# tvout_terminal_v1_0.net
KiCad netlist of a schematic drawn in EAGLE
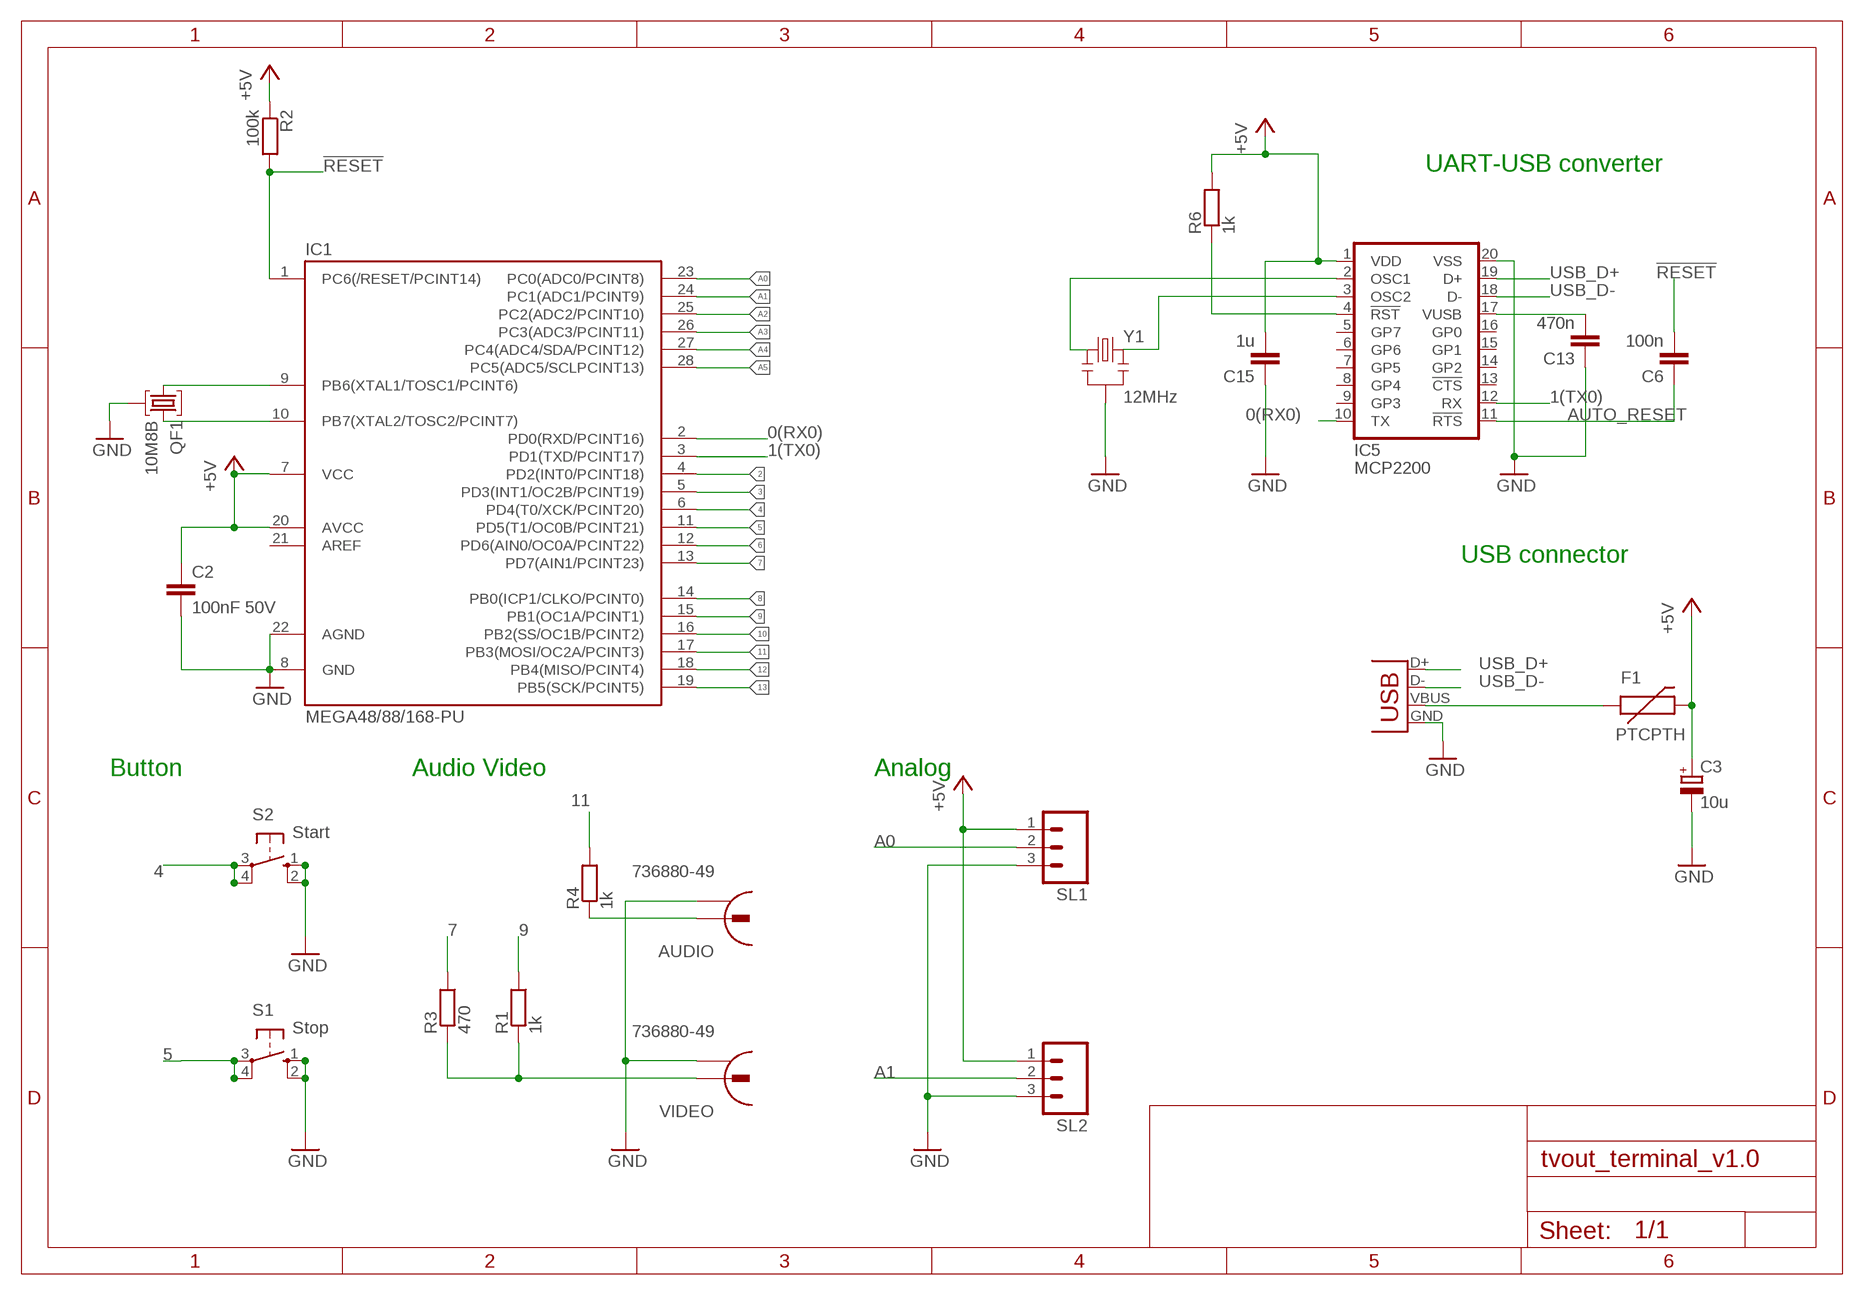
[diagram p0: schematic, sheet 1]

(export (version "E")
  (design (tool "Eeschema 10.0.6"))
  (components
    (comp (ref "AUDIO")
      (value "736880-49")
      (footprint "eagle-import:736880-49")
      (libsource (lib "eagle-import") (part "736880-49"))
    )
    (comp (ref "C2")
      (value "100nF 50V")
      (footprint "eagle-import:C025-025X050")
      (libsource (lib "eagle-import") (part "C-EU025-025X050"))
    )
    (comp (ref "C3")
      (value "10u")
      (footprint "eagle-import:E2,5-7")
      (libsource (lib "eagle-import") (part "CPOL-EUE2.5-7"))
    )
    (comp (ref "C6")
      (value "100n")
      (footprint "eagle-import:CAP-PTH-SMALL")
      (libsource (lib "eagle-import") (part "CAPPTH"))
    )
    (comp (ref "C13")
      (value "470n")
      (footprint "eagle-import:CAP-PTH-SMALL")
      (libsource (lib "eagle-import") (part "CAPPTH"))
    )
    (comp (ref "C15")
      (value "1u")
      (footprint "eagle-import:CAP-PTH-SMALL")
      (libsource (lib "eagle-import") (part "CAPPTH"))
    )
    (comp (ref "F1")
      (value "PTCPTH")
      (footprint "eagle-import:PTC")
      (libsource (lib "eagle-import") (part "PTCPTH"))
    )
    (comp (ref "IC1")
      (value "MEGA48/88/168-PU")
      (footprint "eagle-import:DIL28-3")
      (libsource (lib "eagle-import") (part "MEGA48/88/168-PU"))
    )
    (comp (ref "IC5")
      (value "MCP2200")
      (footprint "eagle-import:SO20")
      (libsource (lib "eagle-import") (part "MCP2200"))
    )
    (comp (ref "QF1")
      (value "10M8B")
      (footprint "eagle-import:HC49U")
      (fields (field (name "OC_FARNELL") "1448129"))
      (libsource (lib "eagle-import") (part "10MB8"))
    )
    (comp (ref "R1")
      (value "1k")
      (footprint "eagle-import:RES-AXIAL-0.4")
      (libsource (lib "eagle-import") (part "RESISTOR"))
    )
    (comp (ref "R2")
      (value "100k")
      (footprint "eagle-import:RES-AXIAL-0.4")
      (libsource (lib "eagle-import") (part "RESISTOR"))
    )
    (comp (ref "R3")
      (value "470")
      (footprint "eagle-import:RES-AXIAL-0.4")
      (libsource (lib "eagle-import") (part "RESISTOR"))
    )
    (comp (ref "R4")
      (value "1k")
      (footprint "eagle-import:RES-AXIAL-0.4")
      (libsource (lib "eagle-import") (part "RESISTOR"))
    )
    (comp (ref "R6")
      (value "1k")
      (footprint "eagle-import:RES-AXIAL-0.4")
      (libsource (lib "eagle-import") (part "RESISTOR"))
    )
    (comp (ref "S1")
      (value "Stop")
      (footprint "eagle-import:B3F-10XX")
      (fields (field (name "MPN") "B3F-1000"))
      (libsource (lib "eagle-import") (part "10-XX"))
    )
    (comp (ref "S2")
      (value "Start")
      (footprint "eagle-import:B3F-10XX")
      (fields (field (name "MPN") "B3F-1000"))
      (libsource (lib "eagle-import") (part "10-XX"))
    )
    (comp (ref "SL1")
      (value "M03")
      (footprint "eagle-import:03P")
      (fields (field (name "OC_FARNELL") "1675765"))
      (libsource (lib "eagle-import") (part "M03"))
    )
    (comp (ref "SL2")
      (value "M03")
      (footprint "eagle-import:03P")
      (libsource (lib "eagle-import") (part "M03"))
    )
    (comp (ref "VIDEO")
      (value "736880-49")
      (footprint "eagle-import:736880-49")
      (libsource (lib "eagle-import") (part "736880-49"))
    )
    (comp (ref "X3")
      (value "USB")
      (footprint "eagle-import:USB-B-PTH")
      (libsource (lib "eagle-import") (part "USBPTH"))
    )
    (comp (ref "Y1")
      (value "12MHz")
      (footprint "eagle-import:HC49U-V-RESONATOR")
      (libsource (lib "eagle-import") (part "CRYSTAL-RESONATOR"))
    )
  )
  (nets
    (net (code "1") (name "+5V") (class "Default")
      (node (ref "C15") (pin "2") (pinfunction "2_2") (pintype "passive"))
      (node (ref "C2") (pin "1") (pinfunction "1_1") (pintype "passive"))
      (node (ref "C3") (pin "+") (pinfunction "+_+") (pintype "passive"))
      (node (ref "F1") (pin "P$2") (pinfunction "2_P$2") (pintype "bidirectional"))
      (node (ref "IC1") (pin "20") (pinfunction "AVCC_20") (pintype "passive"))
      (node (ref "IC1") (pin "7") (pinfunction "VCC_7") (pintype "power_in"))
      (node (ref "IC5") (pin "1") (pinfunction "VDD_1") (pintype "power_in"))
      (node (ref "R2") (pin "P$1") (pinfunction "1_P$1") (pintype "passive"))
      (node (ref "R6") (pin "P$2") (pinfunction "2_P$2") (pintype "passive"))
      (node (ref "SL1") (pin "1") (pinfunction "1_1") (pintype "passive"))
      (node (ref "SL2") (pin "1") (pinfunction "1_1") (pintype "passive"))
    )
    (net (code "2") (name "/0(RX0)") (class "Default")
      (node (ref "IC1") (pin "2") (pinfunction "PD0(RXD/PCINT16)_2") (pintype "bidirectional"))
      (node (ref "IC5") (pin "10") (pinfunction "TX_10") (pintype "bidirectional"))
    )
    (net (code "3") (name "/1(TX0)") (class "Default")
      (node (ref "IC1") (pin "3") (pinfunction "PD1(TXD/PCINT17)_3") (pintype "bidirectional"))
      (node (ref "IC5") (pin "12") (pinfunction "RX_12") (pintype "bidirectional"))
    )
    (net (code "4") (name "/AUTO_RESET") (class "Default")
      (node (ref "C6") (pin "1") (pinfunction "1_1") (pintype "passive"))
      (node (ref "IC5") (pin "11") (pinfunction "~{RTS}_11") (pintype "bidirectional"))
    )
    (net (code "5") (name "/USB_D+") (class "Default")
      (node (ref "IC5") (pin "19") (pinfunction "D+_19") (pintype "bidirectional"))
      (node (ref "X3") (pin "D+") (pinfunction "D+_D+") (pintype "bidirectional"))
    )
    (net (code "6") (name "/USB_D-") (class "Default")
      (node (ref "IC5") (pin "18") (pinfunction "D-_18") (pintype "bidirectional"))
      (node (ref "X3") (pin "D-") (pinfunction "D-_D-") (pintype "bidirectional"))
    )
    (net (code "7") (name "/~{RESET}") (class "Default")
      (node (ref "C6") (pin "2") (pinfunction "2_2") (pintype "passive"))
      (node (ref "IC1") (pin "1") (pinfunction "PC6(/RESET/PCINT14)_1") (pintype "bidirectional"))
      (node (ref "R2") (pin "P$2") (pinfunction "2_P$2") (pintype "passive"))
    )
    (net (code "8") (name "2") (class "Default")
      (node (ref "IC1") (pin "4") (pinfunction "PD2(INT0/PCINT18)_4") (pintype "bidirectional"))
    )
    (net (code "9") (name "3") (class "Default")
      (node (ref "IC1") (pin "5") (pinfunction "PD3(INT1/OC2B/PCINT19)_5") (pintype "bidirectional"))
    )
    (net (code "10") (name "4") (class "Default")
      (node (ref "IC1") (pin "6") (pinfunction "PD4(T0/XCK/PCINT20)_6") (pintype "bidirectional"))
      (node (ref "S2") (pin "3") (pinfunction "P_3") (pintype "passive"))
      (node (ref "S2") (pin "4") (pinfunction "P1_4") (pintype "passive"))
    )
    (net (code "11") (name "5") (class "Default")
      (node (ref "IC1") (pin "11") (pinfunction "PD5(T1/OC0B/PCINT21)_11") (pintype "bidirectional"))
      (node (ref "S1") (pin "3") (pinfunction "P_3") (pintype "passive"))
      (node (ref "S1") (pin "4") (pinfunction "P1_4") (pintype "passive"))
    )
    (net (code "12") (name "6") (class "Default")
      (node (ref "IC1") (pin "12") (pinfunction "PD6(AIN0/OC0A/PCINT22)_12") (pintype "bidirectional"))
    )
    (net (code "13") (name "7") (class "Default")
      (node (ref "IC1") (pin "13") (pinfunction "PD7(AIN1/PCINT23)_13") (pintype "bidirectional"))
      (node (ref "R3") (pin "P$2") (pinfunction "2_P$2") (pintype "passive"))
    )
    (net (code "14") (name "8") (class "Default")
      (node (ref "IC1") (pin "14") (pinfunction "PB0(ICP1/CLKO/PCINT0)_14") (pintype "bidirectional"))
    )
    (net (code "15") (name "9") (class "Default")
      (node (ref "IC1") (pin "15") (pinfunction "PB1(OC1A/PCINT1)_15") (pintype "bidirectional"))
      (node (ref "R1") (pin "P$2") (pinfunction "2_P$2") (pintype "passive"))
    )
    (net (code "16") (name "10") (class "Default")
      (node (ref "IC1") (pin "16") (pinfunction "PB2(SS/OC1B/PCINT2)_16") (pintype "bidirectional"))
    )
    (net (code "17") (name "11") (class "Default")
      (node (ref "IC1") (pin "17") (pinfunction "PB3(MOSI/OC2A/PCINT3)_17") (pintype "bidirectional"))
      (node (ref "R4") (pin "P$2") (pinfunction "2_P$2") (pintype "passive"))
    )
    (net (code "18") (name "12") (class "Default")
      (node (ref "IC1") (pin "18") (pinfunction "PB4(MISO/PCINT4)_18") (pintype "bidirectional"))
    )
    (net (code "19") (name "13") (class "Default")
      (node (ref "IC1") (pin "19") (pinfunction "PB5(SCK/PCINT5)_19") (pintype "bidirectional"))
    )
    (net (code "20") (name "A0") (class "Default")
      (node (ref "IC1") (pin "23") (pinfunction "PC0(ADC0/PCINT8)_23") (pintype "bidirectional"))
      (node (ref "SL1") (pin "2") (pinfunction "2_2") (pintype "passive"))
    )
    (net (code "21") (name "A1") (class "Default")
      (node (ref "IC1") (pin "24") (pinfunction "PC1(ADC1/PCINT9)_24") (pintype "bidirectional"))
      (node (ref "SL2") (pin "2") (pinfunction "2_2") (pintype "passive"))
    )
    (net (code "22") (name "A2") (class "Default")
      (node (ref "IC1") (pin "25") (pinfunction "PC2(ADC2/PCINT10)_25") (pintype "bidirectional"))
    )
    (net (code "23") (name "A3") (class "Default")
      (node (ref "IC1") (pin "26") (pinfunction "PC3(ADC3/PCINT11)_26") (pintype "bidirectional"))
    )
    (net (code "24") (name "A4") (class "Default")
      (node (ref "IC1") (pin "27") (pinfunction "PC4(ADC4/SDA/PCINT12)_27") (pintype "bidirectional"))
    )
    (net (code "25") (name "A5") (class "Default")
      (node (ref "IC1") (pin "28") (pinfunction "PC5(ADC5/SCLPCINT13)_28") (pintype "bidirectional"))
    )
    (net (code "26") (name "GND") (class "Default")
      (node (ref "AUDIO") (pin "2") (pinfunction "2_2") (pintype "passive"))
      (node (ref "C13") (pin "1") (pinfunction "1_1") (pintype "passive"))
      (node (ref "C15") (pin "1") (pinfunction "1_1") (pintype "passive"))
      (node (ref "C2") (pin "2") (pinfunction "2_2") (pintype "passive"))
      (node (ref "C3") (pin "-") (pinfunction "-_-") (pintype "passive"))
      (node (ref "IC1") (pin "22") (pinfunction "AGND_22") (pintype "power_in"))
      (node (ref "IC1") (pin "8") (pinfunction "GND_8") (pintype "power_in"))
      (node (ref "IC5") (pin "20") (pinfunction "VSS_20") (pintype "power_in"))
      (node (ref "QF1") (pin "2") (pinfunction "2_2") (pintype "passive"))
      (node (ref "S1") (pin "1") (pinfunction "S_1") (pintype "passive"))
      (node (ref "S1") (pin "2") (pinfunction "S1_2") (pintype "passive"))
      (node (ref "S2") (pin "1") (pinfunction "S_1") (pintype "passive"))
      (node (ref "S2") (pin "2") (pinfunction "S1_2") (pintype "passive"))
      (node (ref "SL1") (pin "3") (pinfunction "3_3") (pintype "passive"))
      (node (ref "SL2") (pin "3") (pinfunction "3_3") (pintype "passive"))
      (node (ref "VIDEO") (pin "2") (pinfunction "2_2") (pintype "passive"))
      (node (ref "X3") (pin "GND") (pinfunction "GND_GND") (pintype "bidirectional"))
      (node (ref "Y1") (pin "GND") (pinfunction "2_GND") (pintype "passive"))
    )
    (net (code "27") (name "Net-(F1-1)") (class "Default")
      (node (ref "F1") (pin "P$1") (pinfunction "1_P$1") (pintype "bidirectional"))
      (node (ref "X3") (pin "VBUS") (pinfunction "VBUS_VBUS") (pintype "bidirectional"))
    )
    (net (code "28") (name "Net-(IC1-PB6(XTAL1{slash}TOSC1{slash}PCINT6))") (class "Default")
      (node (ref "IC1") (pin "9") (pinfunction "PB6(XTAL1/TOSC1/PCINT6)_9") (pintype "bidirectional"))
      (node (ref "QF1") (pin "1") (pinfunction "1_1") (pintype "passive"))
    )
    (net (code "29") (name "Net-(IC1-PB7(XTAL2{slash}TOSC2{slash}PCINT7))") (class "Default")
      (node (ref "IC1") (pin "10") (pinfunction "PB7(XTAL2/TOSC2/PCINT7)_10") (pintype "bidirectional"))
      (node (ref "QF1") (pin "3") (pinfunction "3_3") (pintype "passive"))
    )
    (net (code "30") (name "Net-(IC5-OSC1)") (class "Default")
      (node (ref "IC5") (pin "2") (pinfunction "OSC1_2") (pintype "bidirectional"))
      (node (ref "Y1") (pin "1") (pinfunction "1_1") (pintype "passive"))
    )
    (net (code "31") (name "Net-(IC5-OSC2)") (class "Default")
      (node (ref "IC5") (pin "3") (pinfunction "OSC2_3") (pintype "bidirectional"))
      (node (ref "Y1") (pin "2") (pinfunction "3_2") (pintype "passive"))
    )
    (net (code "32") (name "Net-(IC5-VUSB)") (class "Default")
      (node (ref "C13") (pin "2") (pinfunction "2_2") (pintype "passive"))
      (node (ref "IC5") (pin "17") (pinfunction "VUSB_17") (pintype "bidirectional"))
    )
    (net (code "33") (name "Net-(IC5-~{RST})") (class "Default")
      (node (ref "IC5") (pin "4") (pinfunction "~{RST}_4") (pintype "bidirectional"))
      (node (ref "R6") (pin "P$1") (pinfunction "1_P$1") (pintype "passive"))
    )
    (net (code "34") (name "Net-(R1-1)") (class "Default")
      (node (ref "R1") (pin "P$1") (pinfunction "1_P$1") (pintype "passive"))
      (node (ref "R3") (pin "P$1") (pinfunction "1_P$1") (pintype "passive"))
      (node (ref "VIDEO") (pin "1") (pinfunction "1_1") (pintype "passive"))
    )
    (net (code "35") (name "Net-(R4-1)") (class "Default")
      (node (ref "AUDIO") (pin "1") (pinfunction "1_1") (pintype "passive"))
      (node (ref "R4") (pin "P$1") (pinfunction "1_P$1") (pintype "passive"))
    )
    (net (code "36") (name "unconnected-(AUDIO-2-Pad2@2)") (class "Default")
      (node (ref "AUDIO") (pin "2@2") (pinfunction "2_2@2") (pintype "passive"))
    )
    (net (code "37") (name "unconnected-(IC1-AREF-Pad21)") (class "Default")
      (node (ref "IC1") (pin "21") (pinfunction "AREF_21") (pintype "passive"))
    )
    (net (code "38") (name "unconnected-(IC5-GP0-Pad16)") (class "Default")
      (node (ref "IC5") (pin "16") (pinfunction "GP0_16") (pintype "bidirectional"))
    )
    (net (code "39") (name "unconnected-(IC5-GP1-Pad15)") (class "Default")
      (node (ref "IC5") (pin "15") (pinfunction "GP1_15") (pintype "bidirectional"))
    )
    (net (code "40") (name "unconnected-(IC5-GP2-Pad14)") (class "Default")
      (node (ref "IC5") (pin "14") (pinfunction "GP2_14") (pintype "bidirectional"))
    )
    (net (code "41") (name "unconnected-(IC5-GP3-Pad9)") (class "Default")
      (node (ref "IC5") (pin "9") (pinfunction "GP3_9") (pintype "bidirectional"))
    )
    (net (code "42") (name "unconnected-(IC5-GP4-Pad8)") (class "Default")
      (node (ref "IC5") (pin "8") (pinfunction "GP4_8") (pintype "bidirectional"))
    )
    (net (code "43") (name "unconnected-(IC5-GP5-Pad7)") (class "Default")
      (node (ref "IC5") (pin "7") (pinfunction "GP5_7") (pintype "bidirectional"))
    )
    (net (code "44") (name "unconnected-(IC5-GP6-Pad6)") (class "Default")
      (node (ref "IC5") (pin "6") (pinfunction "GP6_6") (pintype "bidirectional"))
    )
    (net (code "45") (name "unconnected-(IC5-GP7-Pad5)") (class "Default")
      (node (ref "IC5") (pin "5") (pinfunction "GP7_5") (pintype "bidirectional"))
    )
    (net (code "46") (name "unconnected-(IC5-~{CTS}-Pad13)") (class "Default")
      (node (ref "IC5") (pin "13") (pinfunction "~{CTS}_13") (pintype "bidirectional"))
    )
    (net (code "47") (name "unconnected-(VIDEO-2-Pad2@2)") (class "Default")
      (node (ref "VIDEO") (pin "2@2") (pinfunction "2_2@2") (pintype "passive"))
    )
  )
)
